# KegWasher_1_1_Schematic_EasyEDA.net
KiCad netlist of a schematic drawn in EasyEDA
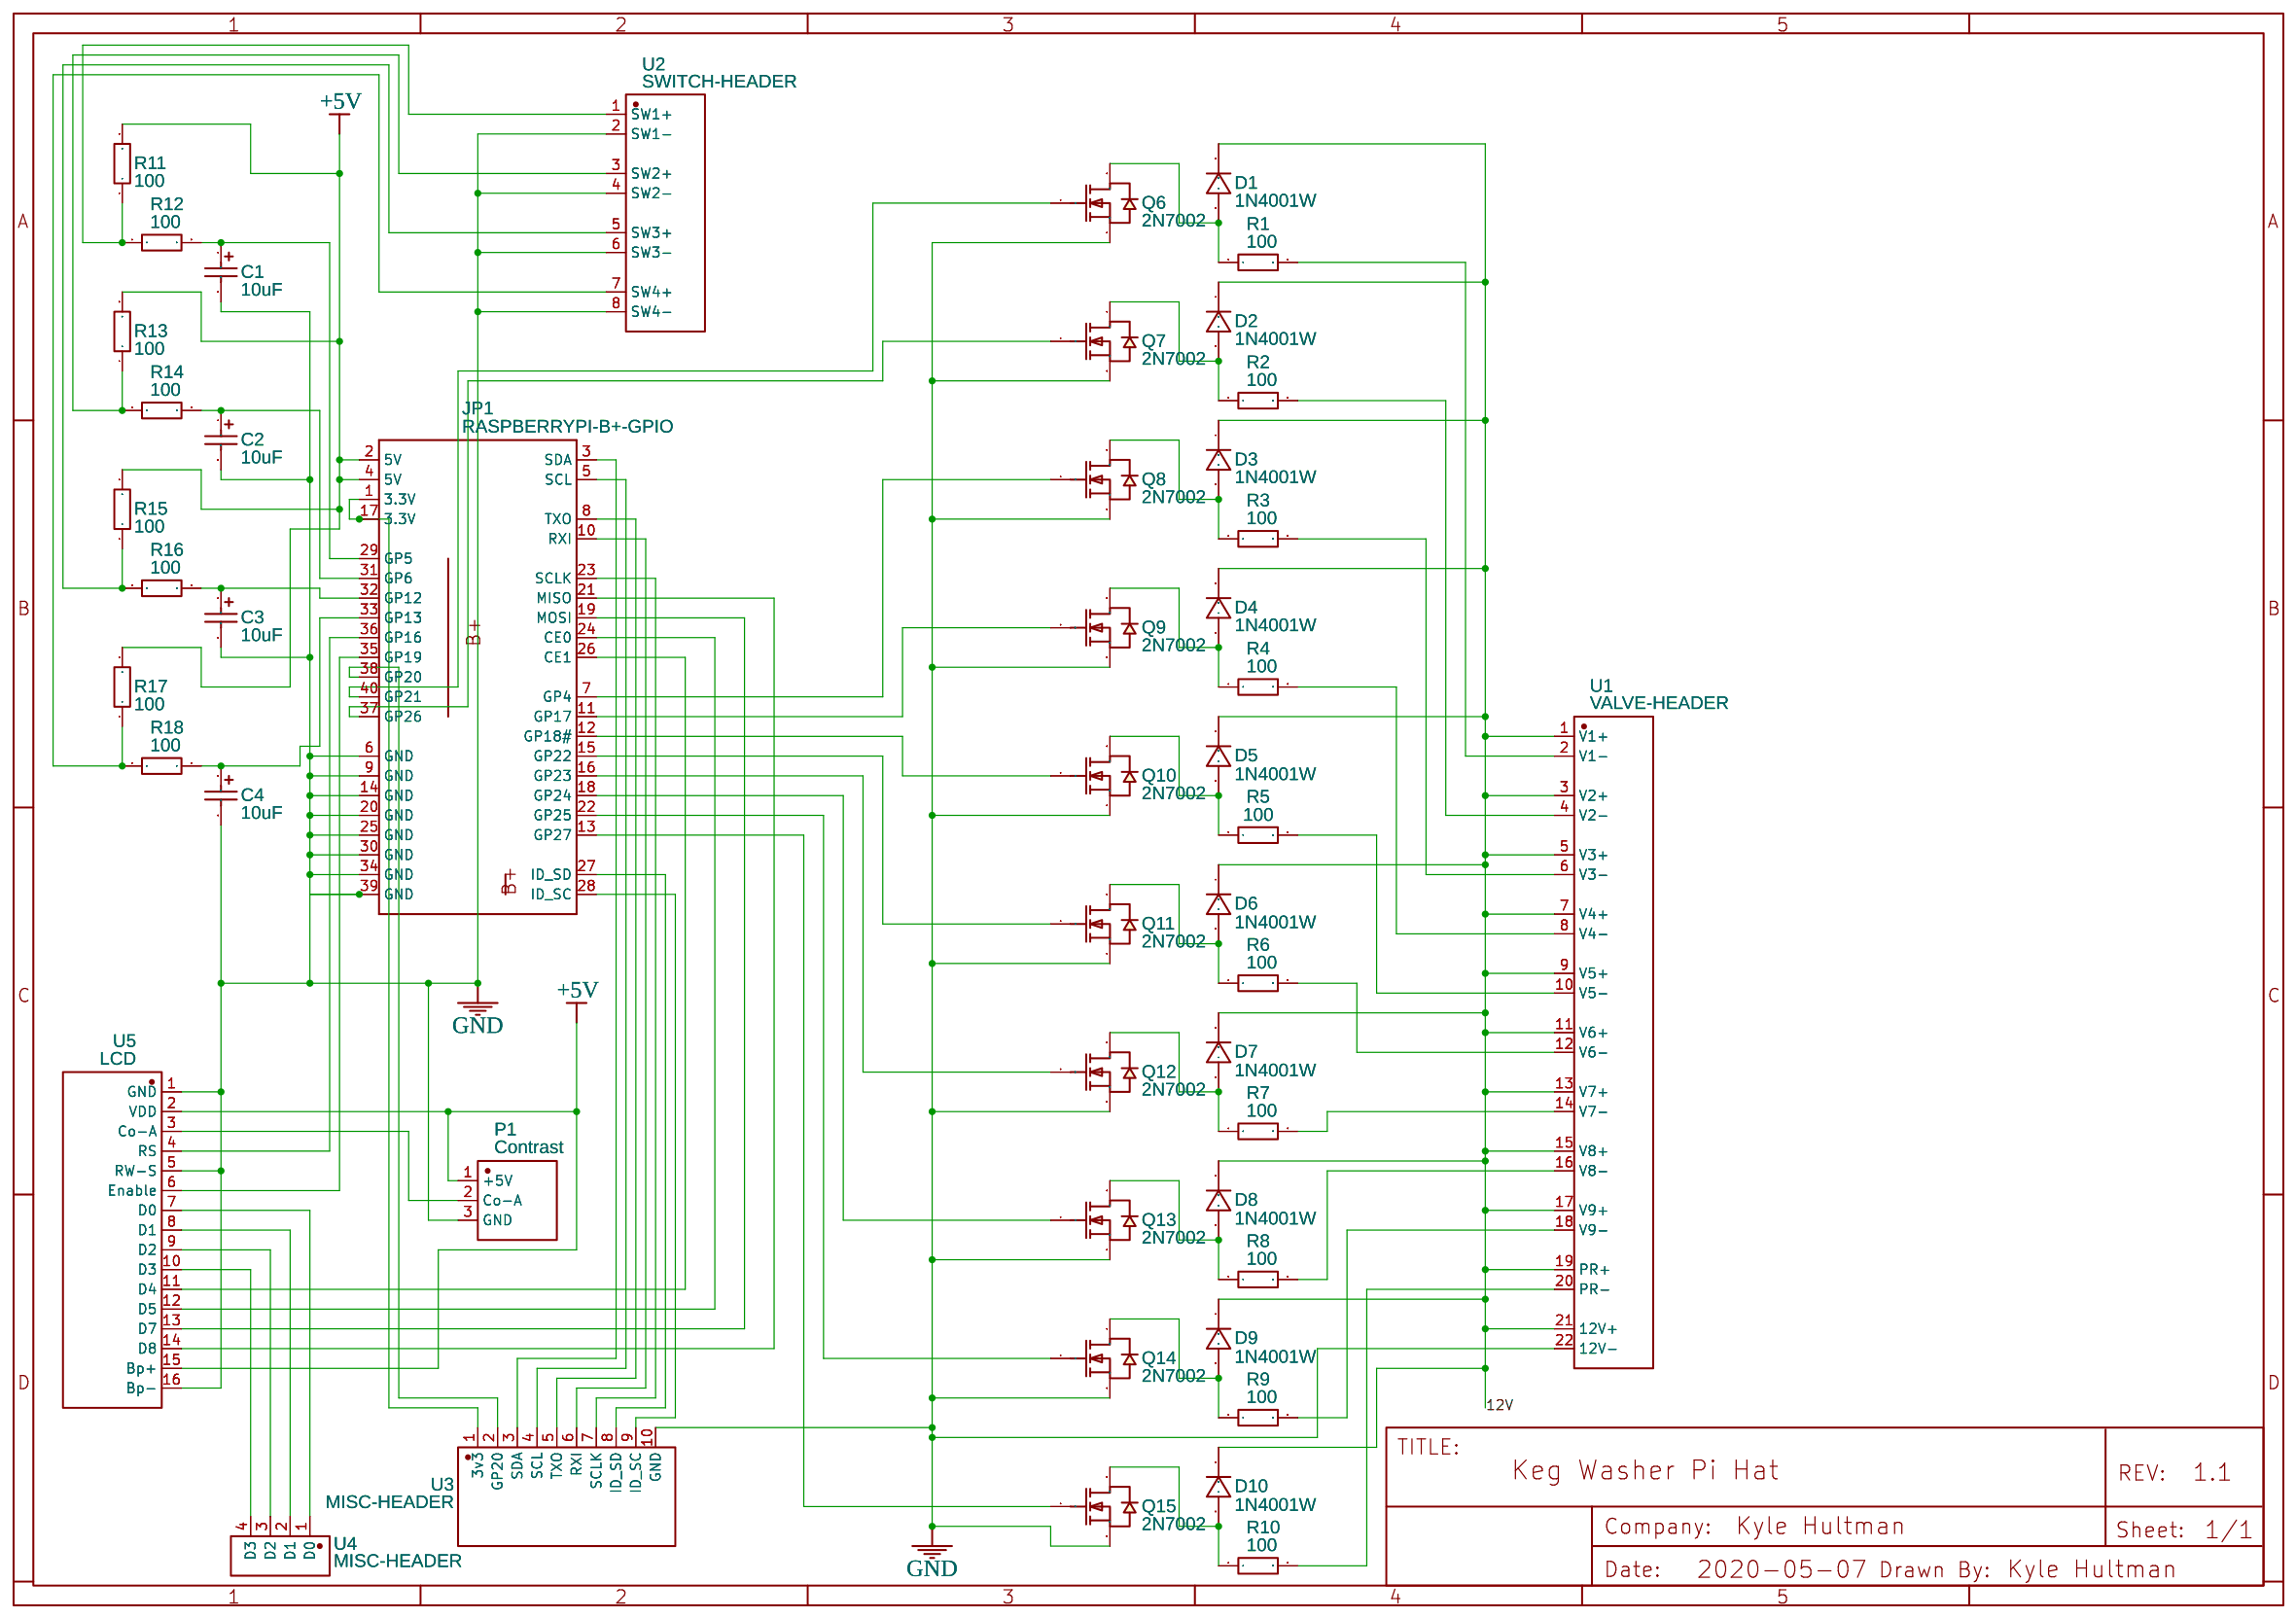
[diagram p0: schematic sheet]

(export (version "E")
  (design (tool "Eeschema 10.0.6"))
  (components
    (comp (ref "C1")
      (value "10uF")
      (fields
        (field (name "BOM_Manufacturer Part") "TAJA106K016RNJ")
        (field (name "BOM_Supplier Part") "C7171")
      )
      (libsource (lib "") (part "TAJA106K016RNJ"))
    )
    (comp (ref "C2")
      (value "10uF")
      (fields
        (field (name "BOM_Manufacturer Part") "TAJA106K016RNJ")
        (field (name "BOM_Supplier Part") "C7171")
      )
      (libsource (lib "") (part "TAJA106K016RNJ"))
    )
    (comp (ref "C3")
      (value "10uF")
      (fields
        (field (name "BOM_Manufacturer Part") "TAJA106K016RNJ")
        (field (name "BOM_Supplier Part") "C7171")
      )
      (libsource (lib "") (part "TAJA106K016RNJ"))
    )
    (comp (ref "C4")
      (value "10uF")
      (fields
        (field (name "BOM_Manufacturer Part") "TAJA106K016RNJ")
        (field (name "BOM_Supplier Part") "C7171")
      )
      (libsource (lib "") (part "TAJA106K016RNJ"))
    )
    (comp (ref "D1")
      (value "1N4001W")
      (fields (field (name "BOM_Supplier Part") "C162732"))
      (libsource (lib "") (part "1N4001W"))
    )
    (comp (ref "D2")
      (value "1N4001W")
      (fields (field (name "BOM_Supplier Part") "C162732"))
      (libsource (lib "") (part "1N4001W"))
    )
    (comp (ref "D3")
      (value "1N4001W")
      (fields (field (name "BOM_Supplier Part") "C162732"))
      (libsource (lib "") (part "1N4001W"))
    )
    (comp (ref "D4")
      (value "1N4001W")
      (fields (field (name "BOM_Supplier Part") "C162732"))
      (libsource (lib "") (part "1N4001W"))
    )
    (comp (ref "D5")
      (value "1N4001W")
      (fields (field (name "BOM_Supplier Part") "C162732"))
      (libsource (lib "") (part "1N4001W"))
    )
    (comp (ref "D6")
      (value "1N4001W")
      (fields (field (name "BOM_Supplier Part") "C162732"))
      (libsource (lib "") (part "1N4001W"))
    )
    (comp (ref "D7")
      (value "1N4001W")
      (fields (field (name "BOM_Supplier Part") "C162732"))
      (libsource (lib "") (part "1N4001W"))
    )
    (comp (ref "D8")
      (value "1N4001W")
      (fields (field (name "BOM_Supplier Part") "C162732"))
      (libsource (lib "") (part "1N4001W"))
    )
    (comp (ref "D9")
      (value "1N4001W")
      (fields (field (name "BOM_Supplier Part") "C162732"))
      (libsource (lib "") (part "1N4001W"))
    )
    (comp (ref "D10")
      (value "1N4001W")
      (fields (field (name "BOM_Supplier Part") "C162732"))
      (libsource (lib "") (part "1N4001W"))
    )
    (comp (ref "JP1") (value "RASPBERRYPI-B+-GPIO") (libsource (lib "") (part "RASPBERRYPI-B+-GPIO")))
    (comp (ref "P1") (value "Contrast") (libsource (lib "") (part "Contrast")))
    (comp (ref "Q6")
      (value "2N7002")
      (fields (field (name "BOM_Supplier Part") "C8545"))
      (libsource (lib "") (part "2N7002"))
    )
    (comp (ref "Q7")
      (value "2N7002")
      (fields (field (name "BOM_Supplier Part") "C8545"))
      (libsource (lib "") (part "2N7002"))
    )
    (comp (ref "Q8")
      (value "2N7002")
      (fields (field (name "BOM_Supplier Part") "C8545"))
      (libsource (lib "") (part "2N7002"))
    )
    (comp (ref "Q9")
      (value "2N7002")
      (fields (field (name "BOM_Supplier Part") "C8545"))
      (libsource (lib "") (part "2N7002"))
    )
    (comp (ref "Q10")
      (value "2N7002")
      (fields (field (name "BOM_Supplier Part") "C8545"))
      (libsource (lib "") (part "2N7002"))
    )
    (comp (ref "Q11")
      (value "2N7002")
      (fields (field (name "BOM_Supplier Part") "C8545"))
      (libsource (lib "") (part "2N7002"))
    )
    (comp (ref "Q12")
      (value "2N7002")
      (fields (field (name "BOM_Supplier Part") "C8545"))
      (libsource (lib "") (part "2N7002"))
    )
    (comp (ref "Q13")
      (value "2N7002")
      (fields (field (name "BOM_Supplier Part") "C8545"))
      (libsource (lib "") (part "2N7002"))
    )
    (comp (ref "Q14")
      (value "2N7002")
      (fields (field (name "BOM_Supplier Part") "C8545"))
      (libsource (lib "") (part "2N7002"))
    )
    (comp (ref "Q15")
      (value "2N7002")
      (fields (field (name "BOM_Supplier Part") "C8545"))
      (libsource (lib "") (part "2N7002"))
    )
    (comp (ref "R1")
      (value "100")
      (fields
        (field (name "BOM_Manufacturer Part") "0805W8F1000T5E")
        (field (name "BOM_Supplier Part") "C17408")
      )
      (libsource (lib "") (part "0805W8F1000T5E_1"))
    )
    (comp (ref "R2")
      (value "100")
      (fields
        (field (name "BOM_Manufacturer Part") "0805W8F1000T5E")
        (field (name "BOM_Supplier Part") "C17408")
      )
      (libsource (lib "") (part "0805W8F1000T5E_1"))
    )
    (comp (ref "R3")
      (value "100")
      (fields
        (field (name "BOM_Manufacturer Part") "0805W8F1000T5E")
        (field (name "BOM_Supplier Part") "C17408")
      )
      (libsource (lib "") (part "0805W8F1000T5E_1"))
    )
    (comp (ref "R4")
      (value "100")
      (fields
        (field (name "BOM_Manufacturer Part") "0805W8F1000T5E")
        (field (name "BOM_Supplier Part") "C17408")
      )
      (libsource (lib "") (part "0805W8F1000T5E_1"))
    )
    (comp (ref "R5")
      (value "100")
      (fields
        (field (name "BOM_Manufacturer Part") "0805W8F1000T5E")
        (field (name "BOM_Supplier Part") "C17408")
      )
      (libsource (lib "") (part "0805W8F1000T5E_1"))
    )
    (comp (ref "R6")
      (value "100")
      (fields
        (field (name "BOM_Manufacturer Part") "0805W8F1000T5E")
        (field (name "BOM_Supplier Part") "C17408")
      )
      (libsource (lib "") (part "0805W8F1000T5E_1"))
    )
    (comp (ref "R7")
      (value "100")
      (fields
        (field (name "BOM_Manufacturer Part") "0805W8F1000T5E")
        (field (name "BOM_Supplier Part") "C17408")
      )
      (libsource (lib "") (part "0805W8F1000T5E_1"))
    )
    (comp (ref "R8")
      (value "100")
      (fields
        (field (name "BOM_Manufacturer Part") "0805W8F1000T5E")
        (field (name "BOM_Supplier Part") "C17408")
      )
      (libsource (lib "") (part "0805W8F1000T5E_1"))
    )
    (comp (ref "R9")
      (value "100")
      (fields
        (field (name "BOM_Manufacturer Part") "0805W8F1000T5E")
        (field (name "BOM_Supplier Part") "C17408")
      )
      (libsource (lib "") (part "0805W8F1000T5E_1"))
    )
    (comp (ref "R10")
      (value "100")
      (fields
        (field (name "BOM_Manufacturer Part") "0805W8F1000T5E")
        (field (name "BOM_Supplier Part") "C17408")
      )
      (libsource (lib "") (part "0805W8F1000T5E_1"))
    )
    (comp (ref "R11")
      (value "100")
      (fields
        (field (name "BOM_Manufacturer Part") "0805W8F1000T5E")
        (field (name "BOM_Supplier Part") "C17408")
      )
      (libsource (lib "") (part "0805W8F1000T5E"))
    )
    (comp (ref "R12")
      (value "100")
      (fields
        (field (name "BOM_Manufacturer Part") "0805W8F1000T5E")
        (field (name "BOM_Supplier Part") "C17408")
      )
      (libsource (lib "") (part "0805W8F1000T5E_1"))
    )
    (comp (ref "R13")
      (value "100")
      (fields
        (field (name "BOM_Manufacturer Part") "0805W8F1000T5E")
        (field (name "BOM_Supplier Part") "C17408")
      )
      (libsource (lib "") (part "0805W8F1000T5E"))
    )
    (comp (ref "R14")
      (value "100")
      (fields
        (field (name "BOM_Manufacturer Part") "0805W8F1000T5E")
        (field (name "BOM_Supplier Part") "C17408")
      )
      (libsource (lib "") (part "0805W8F1000T5E_1"))
    )
    (comp (ref "R15")
      (value "100")
      (fields
        (field (name "BOM_Manufacturer Part") "0805W8F1000T5E")
        (field (name "BOM_Supplier Part") "C17408")
      )
      (libsource (lib "") (part "0805W8F1000T5E"))
    )
    (comp (ref "R16")
      (value "100")
      (fields
        (field (name "BOM_Manufacturer Part") "0805W8F1000T5E")
        (field (name "BOM_Supplier Part") "C17408")
      )
      (libsource (lib "") (part "0805W8F1000T5E_1"))
    )
    (comp (ref "R17")
      (value "100")
      (fields
        (field (name "BOM_Manufacturer Part") "0805W8F1000T5E")
        (field (name "BOM_Supplier Part") "C17408")
      )
      (libsource (lib "") (part "0805W8F1000T5E"))
    )
    (comp (ref "R18")
      (value "100")
      (fields
        (field (name "BOM_Manufacturer Part") "0805W8F1000T5E")
        (field (name "BOM_Supplier Part") "C17408")
      )
      (libsource (lib "") (part "0805W8F1000T5E_1"))
    )
    (comp (ref "U1") (value "VALVE-HEADER") (libsource (lib "") (part "VALVE-HEADER")))
    (comp (ref "U2") (value "SWITCH-HEADER") (libsource (lib "") (part "SWITCH-HEADER")))
    (comp (ref "U3") (value "MISC-HEADER") (libsource (lib "") (part "MISC-HEADER")))
    (comp (ref "U4") (value "MISC-HEADER") (libsource (lib "") (part "MISC-HEADER_1")))
    (comp (ref "U5") (value "LCD") (libsource (lib "") (part "LCD")))
  )
  (nets
    (net (code "1") (name "+5V") (class "Default")
      (node (ref "JP1") (pin "2") (pinfunction "5V_2") (pintype "passive"))
      (node (ref "JP1") (pin "4") (pinfunction "5V_4") (pintype "passive"))
      (node (ref "P1") (pin "1") (pinfunction "+5V_1") (pintype "unspecified"))
      (node (ref "R11") (pin "2") (pinfunction "2_2") (pintype "input"))
      (node (ref "R13") (pin "2") (pinfunction "2_2") (pintype "input"))
      (node (ref "R15") (pin "2") (pinfunction "2_2") (pintype "input"))
      (node (ref "R17") (pin "2") (pinfunction "2_2") (pintype "input"))
      (node (ref "U5") (pin "15") (pinfunction "Bp+_15") (pintype "unspecified"))
      (node (ref "U5") (pin "2") (pinfunction "VDD_2") (pintype "unspecified"))
    )
    (net (code "2") (name "/12V") (class "Default")
      (node (ref "D1") (pin "1") (pinfunction "C_1") (pintype "unspecified"))
      (node (ref "D10") (pin "1") (pinfunction "C_1") (pintype "unspecified"))
      (node (ref "D2") (pin "1") (pinfunction "C_1") (pintype "unspecified"))
      (node (ref "D3") (pin "1") (pinfunction "C_1") (pintype "unspecified"))
      (node (ref "D4") (pin "1") (pinfunction "C_1") (pintype "unspecified"))
      (node (ref "D5") (pin "1") (pinfunction "C_1") (pintype "unspecified"))
      (node (ref "D6") (pin "1") (pinfunction "C_1") (pintype "unspecified"))
      (node (ref "D7") (pin "1") (pinfunction "C_1") (pintype "unspecified"))
      (node (ref "D8") (pin "1") (pinfunction "C_1") (pintype "unspecified"))
      (node (ref "D9") (pin "1") (pinfunction "C_1") (pintype "unspecified"))
      (node (ref "U1") (pin "1") (pinfunction "V1+_1") (pintype "unspecified"))
      (node (ref "U1") (pin "11") (pinfunction "V6+_11") (pintype "unspecified"))
      (node (ref "U1") (pin "13") (pinfunction "V7+_13") (pintype "unspecified"))
      (node (ref "U1") (pin "15") (pinfunction "V8+_15") (pintype "unspecified"))
      (node (ref "U1") (pin "17") (pinfunction "V9+_17") (pintype "unspecified"))
      (node (ref "U1") (pin "19") (pinfunction "PR+_19") (pintype "unspecified"))
      (node (ref "U1") (pin "21") (pinfunction "12V+_21") (pintype "unspecified"))
      (node (ref "U1") (pin "3") (pinfunction "V2+_3") (pintype "unspecified"))
      (node (ref "U1") (pin "5") (pinfunction "V3+_5") (pintype "unspecified"))
      (node (ref "U1") (pin "7") (pinfunction "V4+_7") (pintype "unspecified"))
      (node (ref "U1") (pin "9") (pinfunction "V5+_9") (pintype "unspecified"))
    )
    (net (code "3") (name "GND") (class "Default")
      (node (ref "C1") (pin "2") (pinfunction "2_2") (pintype "input"))
      (node (ref "C2") (pin "2") (pinfunction "2_2") (pintype "input"))
      (node (ref "C3") (pin "2") (pinfunction "2_2") (pintype "input"))
      (node (ref "C4") (pin "2") (pinfunction "2_2") (pintype "input"))
      (node (ref "JP1") (pin "14") (pinfunction "GND_14") (pintype "passive"))
      (node (ref "JP1") (pin "20") (pinfunction "GND_20") (pintype "passive"))
      (node (ref "JP1") (pin "25") (pinfunction "GND_25") (pintype "passive"))
      (node (ref "JP1") (pin "30") (pinfunction "GND_30") (pintype "passive"))
      (node (ref "JP1") (pin "34") (pinfunction "GND_34") (pintype "passive"))
      (node (ref "JP1") (pin "39") (pinfunction "GND_39") (pintype "passive"))
      (node (ref "JP1") (pin "6") (pinfunction "GND_6") (pintype "passive"))
      (node (ref "JP1") (pin "9") (pinfunction "GND_9") (pintype "passive"))
      (node (ref "P1") (pin "3") (pinfunction "GND_3") (pintype "unspecified"))
      (node (ref "Q10") (pin "2") (pinfunction "S_2") (pintype "unspecified"))
      (node (ref "Q11") (pin "2") (pinfunction "S_2") (pintype "unspecified"))
      (node (ref "Q12") (pin "2") (pinfunction "S_2") (pintype "unspecified"))
      (node (ref "Q13") (pin "2") (pinfunction "S_2") (pintype "unspecified"))
      (node (ref "Q14") (pin "2") (pinfunction "S_2") (pintype "unspecified"))
      (node (ref "Q15") (pin "2") (pinfunction "S_2") (pintype "unspecified"))
      (node (ref "Q6") (pin "2") (pinfunction "S_2") (pintype "unspecified"))
      (node (ref "Q7") (pin "2") (pinfunction "S_2") (pintype "unspecified"))
      (node (ref "Q8") (pin "2") (pinfunction "S_2") (pintype "unspecified"))
      (node (ref "Q9") (pin "2") (pinfunction "S_2") (pintype "unspecified"))
      (node (ref "U1") (pin "22") (pinfunction "12V-_22") (pintype "unspecified"))
      (node (ref "U2") (pin "2") (pinfunction "SW1-_2") (pintype "unspecified"))
      (node (ref "U2") (pin "4") (pinfunction "SW2-_4") (pintype "unspecified"))
      (node (ref "U2") (pin "6") (pinfunction "SW3-_6") (pintype "unspecified"))
      (node (ref "U2") (pin "8") (pinfunction "SW4-_8") (pintype "unspecified"))
      (node (ref "U3") (pin "10") (pinfunction "GND_10") (pintype "unspecified"))
      (node (ref "U5") (pin "1") (pinfunction "GND_1") (pintype "unspecified"))
      (node (ref "U5") (pin "16") (pinfunction "Bp-_16") (pintype "unspecified"))
      (node (ref "U5") (pin "5") (pinfunction "RW-S_5") (pintype "unspecified"))
    )
    (net (code "4") (name "Net-(D1-A)") (class "Default")
      (node (ref "D1") (pin "2") (pinfunction "A_2") (pintype "unspecified"))
      (node (ref "Q6") (pin "3") (pinfunction "D_3") (pintype "unspecified"))
      (node (ref "R1") (pin "1") (pinfunction "1_1") (pintype "input"))
    )
    (net (code "5") (name "Net-(D2-A)") (class "Default")
      (node (ref "D2") (pin "2") (pinfunction "A_2") (pintype "unspecified"))
      (node (ref "Q7") (pin "3") (pinfunction "D_3") (pintype "unspecified"))
      (node (ref "R2") (pin "1") (pinfunction "1_1") (pintype "input"))
    )
    (net (code "6") (name "Net-(D3-A)") (class "Default")
      (node (ref "D3") (pin "2") (pinfunction "A_2") (pintype "unspecified"))
      (node (ref "Q8") (pin "3") (pinfunction "D_3") (pintype "unspecified"))
      (node (ref "R3") (pin "1") (pinfunction "1_1") (pintype "input"))
    )
    (net (code "7") (name "Net-(D4-A)") (class "Default")
      (node (ref "D4") (pin "2") (pinfunction "A_2") (pintype "unspecified"))
      (node (ref "Q9") (pin "3") (pinfunction "D_3") (pintype "unspecified"))
      (node (ref "R4") (pin "1") (pinfunction "1_1") (pintype "input"))
    )
    (net (code "8") (name "Net-(D5-A)") (class "Default")
      (node (ref "D5") (pin "2") (pinfunction "A_2") (pintype "unspecified"))
      (node (ref "Q10") (pin "3") (pinfunction "D_3") (pintype "unspecified"))
      (node (ref "R5") (pin "1") (pinfunction "1_1") (pintype "input"))
    )
    (net (code "9") (name "Net-(D6-A)") (class "Default")
      (node (ref "D6") (pin "2") (pinfunction "A_2") (pintype "unspecified"))
      (node (ref "Q11") (pin "3") (pinfunction "D_3") (pintype "unspecified"))
      (node (ref "R6") (pin "1") (pinfunction "1_1") (pintype "input"))
    )
    (net (code "10") (name "Net-(D7-A)") (class "Default")
      (node (ref "D7") (pin "2") (pinfunction "A_2") (pintype "unspecified"))
      (node (ref "Q12") (pin "3") (pinfunction "D_3") (pintype "unspecified"))
      (node (ref "R7") (pin "1") (pinfunction "1_1") (pintype "input"))
    )
    (net (code "11") (name "Net-(D8-A)") (class "Default")
      (node (ref "D8") (pin "2") (pinfunction "A_2") (pintype "unspecified"))
      (node (ref "Q13") (pin "3") (pinfunction "D_3") (pintype "unspecified"))
      (node (ref "R8") (pin "1") (pinfunction "1_1") (pintype "input"))
    )
    (net (code "12") (name "Net-(D9-A)") (class "Default")
      (node (ref "D9") (pin "2") (pinfunction "A_2") (pintype "unspecified"))
      (node (ref "Q14") (pin "3") (pinfunction "D_3") (pintype "unspecified"))
      (node (ref "R9") (pin "1") (pinfunction "1_1") (pintype "input"))
    )
    (net (code "13") (name "Net-(D10-A)") (class "Default")
      (node (ref "D10") (pin "2") (pinfunction "A_2") (pintype "unspecified"))
      (node (ref "Q15") (pin "3") (pinfunction "D_3") (pintype "unspecified"))
      (node (ref "R10") (pin "1") (pinfunction "1_1") (pintype "input"))
    )
    (net (code "14") (name "Net-(JP1-CE0)") (class "Default")
      (node (ref "JP1") (pin "24") (pinfunction "CE0_24") (pintype "output"))
      (node (ref "U5") (pin "12") (pinfunction "D5_12") (pintype "unspecified"))
    )
    (net (code "15") (name "Net-(JP1-CE1)") (class "Default")
      (node (ref "JP1") (pin "26") (pinfunction "CE1_26") (pintype "output"))
      (node (ref "U5") (pin "11") (pinfunction "D4_11") (pintype "unspecified"))
    )
    (net (code "16") (name "Net-(JP1-GP4)") (class "Default")
      (node (ref "JP1") (pin "7") (pinfunction "GP4_7") (pintype "unspecified"))
      (node (ref "Q8") (pin "1") (pinfunction "G_1") (pintype "unspecified"))
    )
    (net (code "17") (name "Net-(JP1-GP5)") (class "Default")
      (node (ref "C1") (pin "1") (pinfunction "1_1") (pintype "input"))
      (node (ref "JP1") (pin "29") (pinfunction "GP5_29") (pintype "unspecified"))
      (node (ref "R12") (pin "2") (pinfunction "2_2") (pintype "input"))
    )
    (net (code "18") (name "Net-(JP1-GP6)") (class "Default")
      (node (ref "C2") (pin "1") (pinfunction "1_1") (pintype "input"))
      (node (ref "JP1") (pin "31") (pinfunction "GP6_31") (pintype "unspecified"))
      (node (ref "R14") (pin "2") (pinfunction "2_2") (pintype "input"))
    )
    (net (code "19") (name "Net-(JP1-GP12)") (class "Default")
      (node (ref "C3") (pin "1") (pinfunction "1_1") (pintype "input"))
      (node (ref "JP1") (pin "32") (pinfunction "GP12_32") (pintype "unspecified"))
      (node (ref "R16") (pin "2") (pinfunction "2_2") (pintype "input"))
    )
    (net (code "20") (name "Net-(JP1-GP13)") (class "Default")
      (node (ref "C4") (pin "1") (pinfunction "1_1") (pintype "input"))
      (node (ref "JP1") (pin "33") (pinfunction "GP13_33") (pintype "unspecified"))
      (node (ref "R18") (pin "2") (pinfunction "2_2") (pintype "input"))
    )
    (net (code "21") (name "Net-(JP1-GP16)") (class "Default")
      (node (ref "JP1") (pin "36") (pinfunction "GP16_36") (pintype "unspecified"))
      (node (ref "U5") (pin "4") (pinfunction "RS_4") (pintype "unspecified"))
    )
    (net (code "22") (name "Net-(JP1-GP17)") (class "Default")
      (node (ref "JP1") (pin "11") (pinfunction "GP17_11") (pintype "unspecified"))
      (node (ref "Q9") (pin "1") (pinfunction "G_1") (pintype "unspecified"))
    )
    (net (code "23") (name "Net-(JP1-GP18#)") (class "Default")
      (node (ref "JP1") (pin "12") (pinfunction "GP18#_12") (pintype "unspecified"))
      (node (ref "Q10") (pin "1") (pinfunction "G_1") (pintype "unspecified"))
    )
    (net (code "24") (name "Net-(JP1-GP19)") (class "Default")
      (node (ref "JP1") (pin "35") (pinfunction "GP19_35") (pintype "unspecified"))
      (node (ref "U5") (pin "6") (pinfunction "Enable_6") (pintype "unspecified"))
    )
    (net (code "25") (name "Net-(JP1-GP20)") (class "Default")
      (node (ref "JP1") (pin "38") (pinfunction "GP20_38") (pintype "unspecified"))
      (node (ref "U3") (pin "2") (pinfunction "GP20_2") (pintype "unspecified"))
    )
    (net (code "26") (name "Net-(JP1-GP21)") (class "Default")
      (node (ref "JP1") (pin "40") (pinfunction "GP21_40") (pintype "unspecified"))
      (node (ref "Q6") (pin "1") (pinfunction "G_1") (pintype "unspecified"))
    )
    (net (code "27") (name "Net-(JP1-GP22)") (class "Default")
      (node (ref "JP1") (pin "15") (pinfunction "GP22_15") (pintype "unspecified"))
      (node (ref "Q11") (pin "1") (pinfunction "G_1") (pintype "unspecified"))
    )
    (net (code "28") (name "Net-(JP1-GP23)") (class "Default")
      (node (ref "JP1") (pin "16") (pinfunction "GP23_16") (pintype "unspecified"))
      (node (ref "Q12") (pin "1") (pinfunction "G_1") (pintype "unspecified"))
    )
    (net (code "29") (name "Net-(JP1-GP24)") (class "Default")
      (node (ref "JP1") (pin "18") (pinfunction "GP24_18") (pintype "unspecified"))
      (node (ref "Q13") (pin "1") (pinfunction "G_1") (pintype "unspecified"))
    )
    (net (code "30") (name "Net-(JP1-GP25)") (class "Default")
      (node (ref "JP1") (pin "22") (pinfunction "GP25_22") (pintype "unspecified"))
      (node (ref "Q14") (pin "1") (pinfunction "G_1") (pintype "unspecified"))
    )
    (net (code "31") (name "Net-(JP1-GP26)") (class "Default")
      (node (ref "JP1") (pin "37") (pinfunction "GP26_37") (pintype "unspecified"))
      (node (ref "Q7") (pin "1") (pinfunction "G_1") (pintype "unspecified"))
    )
    (net (code "32") (name "Net-(JP1-GP27)") (class "Default")
      (node (ref "JP1") (pin "13") (pinfunction "GP27_13") (pintype "unspecified"))
      (node (ref "Q15") (pin "1") (pinfunction "G_1") (pintype "unspecified"))
    )
    (net (code "33") (name "Net-(JP1-ID_SC)") (class "Default")
      (node (ref "JP1") (pin "28") (pinfunction "ID_SC_28") (pintype "unspecified"))
      (node (ref "U3") (pin "9") (pinfunction "ID_SC_9") (pintype "unspecified"))
    )
    (net (code "34") (name "Net-(JP1-ID_SD)") (class "Default")
      (node (ref "JP1") (pin "27") (pinfunction "ID_SD_27") (pintype "unspecified"))
      (node (ref "U3") (pin "8") (pinfunction "ID_SD_8") (pintype "unspecified"))
    )
    (net (code "35") (name "Net-(JP1-MISO)") (class "Default")
      (node (ref "JP1") (pin "21") (pinfunction "MISO_21") (pintype "input"))
      (node (ref "U5") (pin "14") (pinfunction "D8_14") (pintype "unspecified"))
    )
    (net (code "36") (name "Net-(JP1-MOSI)") (class "Default")
      (node (ref "JP1") (pin "19") (pinfunction "MOSI_19") (pintype "output"))
      (node (ref "U5") (pin "13") (pinfunction "D7_13") (pintype "unspecified"))
    )
    (net (code "37") (name "Net-(JP1-RXI)") (class "Default")
      (node (ref "JP1") (pin "10") (pinfunction "RXI_10") (pintype "input"))
      (node (ref "U3") (pin "6") (pinfunction "RXI_6") (pintype "unspecified"))
    )
    (net (code "38") (name "Net-(JP1-SCL)") (class "Default")
      (node (ref "JP1") (pin "5") (pinfunction "SCL_5") (pintype "unspecified"))
      (node (ref "U3") (pin "4") (pinfunction "SCL_4") (pintype "unspecified"))
    )
    (net (code "39") (name "Net-(JP1-SCLK)") (class "Default")
      (node (ref "JP1") (pin "23") (pinfunction "SCLK_23") (pintype "output"))
      (node (ref "U3") (pin "7") (pinfunction "SCLK_7") (pintype "unspecified"))
    )
    (net (code "40") (name "Net-(JP1-SDA)") (class "Default")
      (node (ref "JP1") (pin "3") (pinfunction "SDA_3") (pintype "unspecified"))
      (node (ref "U3") (pin "3") (pinfunction "SDA_3") (pintype "unspecified"))
    )
    (net (code "41") (name "Net-(JP1-TXO)") (class "Default")
      (node (ref "JP1") (pin "8") (pinfunction "TXO_8") (pintype "output"))
      (node (ref "U3") (pin "5") (pinfunction "TXO_5") (pintype "unspecified"))
    )
    (net (code "42") (name "Net-(P1-Co-A)") (class "Default")
      (node (ref "P1") (pin "2") (pinfunction "Co-A_2") (pintype "unspecified"))
      (node (ref "U5") (pin "3") (pinfunction "Co-A_3") (pintype "unspecified"))
    )
    (net (code "43") (name "Net-(U1-PR-)") (class "Default")
      (node (ref "R10") (pin "2") (pinfunction "2_2") (pintype "input"))
      (node (ref "U1") (pin "20") (pinfunction "PR-_20") (pintype "unspecified"))
    )
    (net (code "44") (name "Net-(U1-V1-)") (class "Default")
      (node (ref "R1") (pin "2") (pinfunction "2_2") (pintype "input"))
      (node (ref "U1") (pin "2") (pinfunction "V1-_2") (pintype "unspecified"))
    )
    (net (code "45") (name "Net-(U1-V2-)") (class "Default")
      (node (ref "R2") (pin "2") (pinfunction "2_2") (pintype "input"))
      (node (ref "U1") (pin "4") (pinfunction "V2-_4") (pintype "unspecified"))
    )
    (net (code "46") (name "Net-(U1-V3-)") (class "Default")
      (node (ref "R3") (pin "2") (pinfunction "2_2") (pintype "input"))
      (node (ref "U1") (pin "6") (pinfunction "V3-_6") (pintype "unspecified"))
    )
    (net (code "47") (name "Net-(U1-V4-)") (class "Default")
      (node (ref "R4") (pin "2") (pinfunction "2_2") (pintype "input"))
      (node (ref "U1") (pin "8") (pinfunction "V4-_8") (pintype "unspecified"))
    )
    (net (code "48") (name "Net-(U1-V5-)") (class "Default")
      (node (ref "R5") (pin "2") (pinfunction "2_2") (pintype "input"))
      (node (ref "U1") (pin "10") (pinfunction "V5-_10") (pintype "unspecified"))
    )
    (net (code "49") (name "Net-(U1-V6-)") (class "Default")
      (node (ref "R6") (pin "2") (pinfunction "2_2") (pintype "input"))
      (node (ref "U1") (pin "12") (pinfunction "V6-_12") (pintype "unspecified"))
    )
    (net (code "50") (name "Net-(U1-V7-)") (class "Default")
      (node (ref "R7") (pin "2") (pinfunction "2_2") (pintype "input"))
      (node (ref "U1") (pin "14") (pinfunction "V7-_14") (pintype "unspecified"))
    )
    (net (code "51") (name "Net-(U1-V8-)") (class "Default")
      (node (ref "R8") (pin "2") (pinfunction "2_2") (pintype "input"))
      (node (ref "U1") (pin "16") (pinfunction "V8-_16") (pintype "unspecified"))
    )
    (net (code "52") (name "Net-(U1-V9-)") (class "Default")
      (node (ref "R9") (pin "2") (pinfunction "2_2") (pintype "input"))
      (node (ref "U1") (pin "18") (pinfunction "V9-_18") (pintype "unspecified"))
    )
    (net (code "53") (name "Net-(U2-SW1+)") (class "Default")
      (node (ref "R11") (pin "1") (pinfunction "1_1") (pintype "input"))
      (node (ref "R12") (pin "1") (pinfunction "1_1") (pintype "input"))
      (node (ref "U2") (pin "1") (pinfunction "SW1+_1") (pintype "unspecified"))
    )
    (net (code "54") (name "Net-(U2-SW2+)") (class "Default")
      (node (ref "R13") (pin "1") (pinfunction "1_1") (pintype "input"))
      (node (ref "R14") (pin "1") (pinfunction "1_1") (pintype "input"))
      (node (ref "U2") (pin "3") (pinfunction "SW2+_3") (pintype "unspecified"))
    )
    (net (code "55") (name "Net-(U2-SW3+)") (class "Default")
      (node (ref "R15") (pin "1") (pinfunction "1_1") (pintype "input"))
      (node (ref "R16") (pin "1") (pinfunction "1_1") (pintype "input"))
      (node (ref "U2") (pin "5") (pinfunction "SW3+_5") (pintype "unspecified"))
    )
    (net (code "56") (name "Net-(U2-SW4+)") (class "Default")
      (node (ref "R17") (pin "1") (pinfunction "1_1") (pintype "input"))
      (node (ref "R18") (pin "1") (pinfunction "1_1") (pintype "input"))
      (node (ref "U2") (pin "7") (pinfunction "SW4+_7") (pintype "unspecified"))
    )
    (net (code "57") (name "Net-(U3-3v3)") (class "Default")
      (node (ref "JP1") (pin "1") (pinfunction "3.3V_1") (pintype "passive"))
      (node (ref "JP1") (pin "17") (pinfunction "3.3V_17") (pintype "passive"))
      (node (ref "U3") (pin "1") (pinfunction "3v3_1") (pintype "unspecified"))
    )
    (net (code "58") (name "Net-(U4-D0)") (class "Default")
      (node (ref "U4") (pin "1") (pinfunction "D0_1") (pintype "unspecified"))
      (node (ref "U5") (pin "7") (pinfunction "D0_7") (pintype "unspecified"))
    )
    (net (code "59") (name "Net-(U4-D1)") (class "Default")
      (node (ref "U4") (pin "2") (pinfunction "D1_2") (pintype "unspecified"))
      (node (ref "U5") (pin "8") (pinfunction "D1_8") (pintype "unspecified"))
    )
    (net (code "60") (name "Net-(U4-D2)") (class "Default")
      (node (ref "U4") (pin "3") (pinfunction "D2_3") (pintype "unspecified"))
      (node (ref "U5") (pin "9") (pinfunction "D2_9") (pintype "unspecified"))
    )
    (net (code "61") (name "Net-(U4-D3)") (class "Default")
      (node (ref "U4") (pin "4") (pinfunction "D3_4") (pintype "unspecified"))
      (node (ref "U5") (pin "10") (pinfunction "D3_10") (pintype "unspecified"))
    )
  )
)
